# ARD.net
KiCad netlist of a schematic drawn in Altium Designer
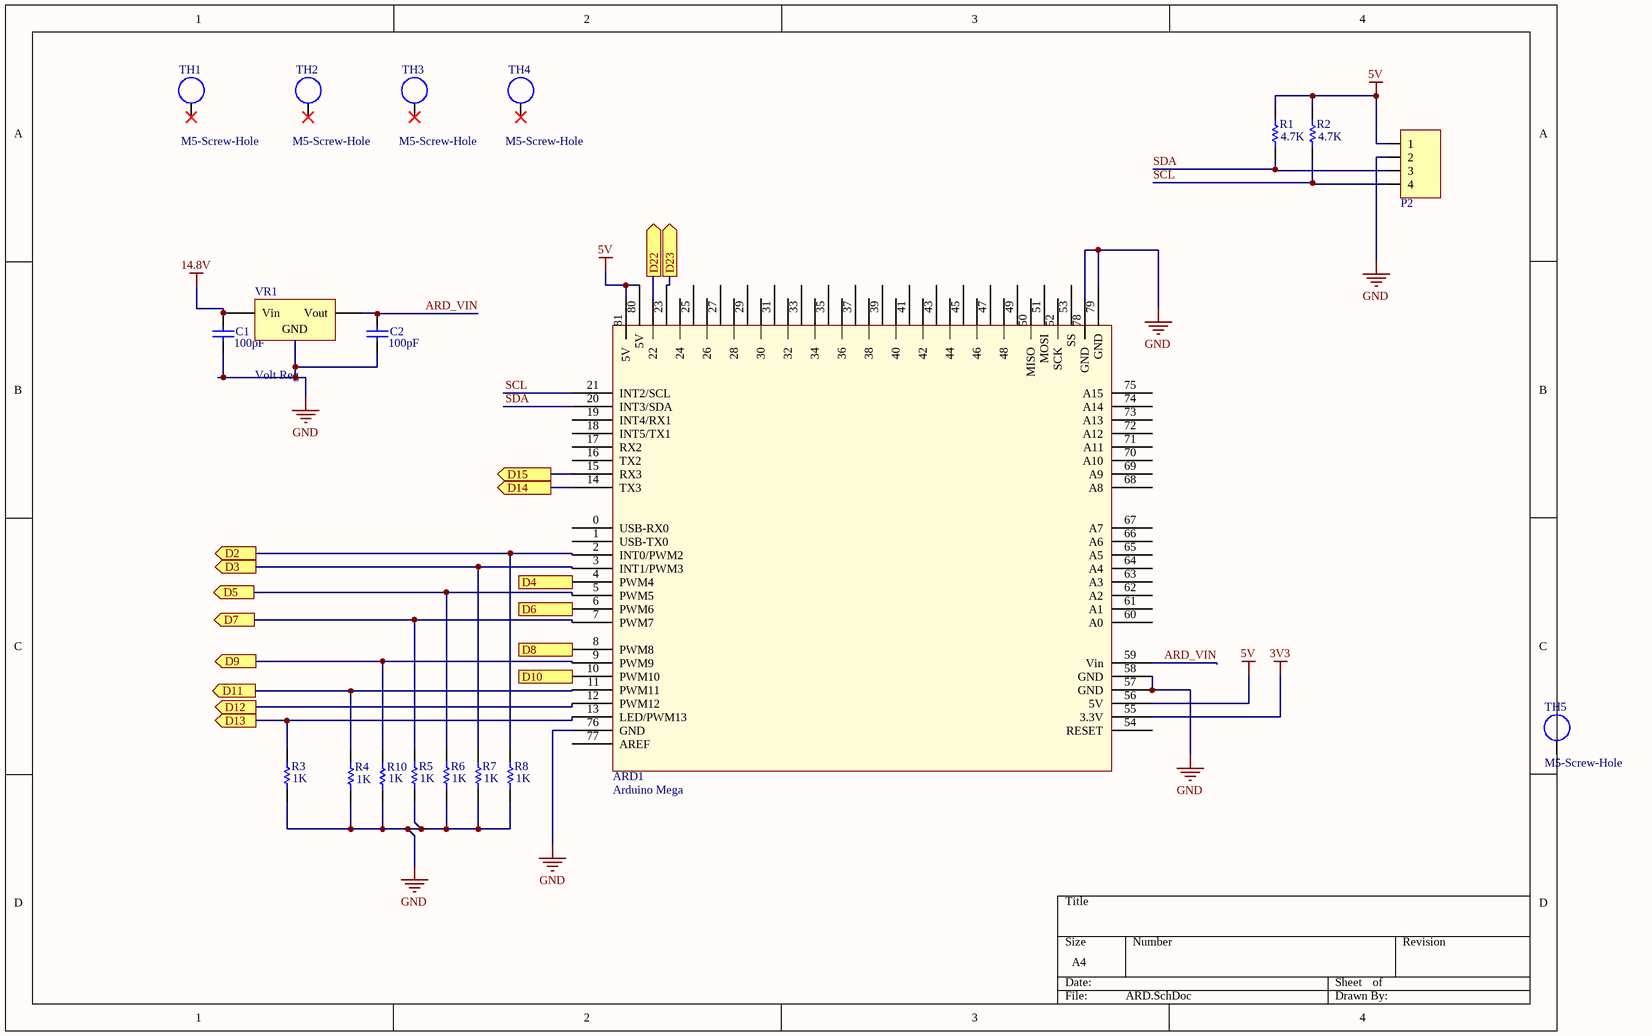
[diagram p0: ARD.SchDoc]

(export (version "E")
  (design (tool "Eeschema 10.0.6"))
  (components
    (comp (ref "ARD1")
      (value "Arduino Mega")
      (footprint "Arduino Mega")
      (libsource (lib "RSX_Modules") (part "Arduino Mega"))
    )
    (comp (ref "C1")
      (value "100pF")
      (footprint "C1206")
      (description "Capacitor (Semiconductor SIM Model)")
      (fields (field (name "Comment") "Cap Semi") (field (name "PUBLISHER") "Altium Limited"))
      (libsource (lib "Miscellaneous Devices") (part "Cap Semi"))
    )
    (comp (ref "C2")
      (value "100pF")
      (footprint "C1206")
      (description "Capacitor (Semiconductor SIM Model)")
      (fields (field (name "Comment") "Cap Semi") (field (name "PUBLISHER") "Altium Limited"))
      (libsource (lib "Miscellaneous Devices") (part "Cap Semi"))
    )
    (comp (ref "P2")
      (value "Mini-Fit Jr 4 Pos")
      (footprint "MOLEX 0039281043")
      (libsource (lib "RSX_Connectors") (part "Molex 0039281043"))
    )
    (comp (ref "R1")
      (value "4.7K")
      (footprint "RESC1608X06N_0603")
      (description "Resistor")
      (fields (field (name "Comment") "Res1") (field (name "PUBLISHER") "Altium Limited"))
      (libsource (lib "RSX_Resistors") (part "Res1"))
    )
    (comp (ref "R2")
      (value "4.7K")
      (footprint "RESC1608X06N_0603")
      (description "Resistor")
      (fields (field (name "Comment") "Res1") (field (name "PUBLISHER") "Altium Limited"))
      (libsource (lib "RSX_Resistors") (part "Res1"))
    )
    (comp (ref "R3")
      (value "1K")
      (footprint "RESC1608X06N_0603")
      (description "Resistor")
      (fields (field (name "Comment") "Res1") (field (name "PUBLISHER") "Altium Limited"))
      (libsource (lib "RSX_Resistors") (part "Res1"))
    )
    (comp (ref "R4")
      (value "1K")
      (footprint "RESC1608X06N_0603")
      (description "Resistor")
      (fields (field (name "Comment") "Res1") (field (name "PUBLISHER") "Altium Limited"))
      (libsource (lib "RSX_Resistors") (part "Res1"))
    )
    (comp (ref "R5")
      (value "1K")
      (footprint "RESC1608X06N_0603")
      (description "Resistor")
      (fields (field (name "Comment") "Res1") (field (name "PUBLISHER") "Altium Limited"))
      (libsource (lib "RSX_Resistors") (part "Res1"))
    )
    (comp (ref "R6")
      (value "1K")
      (footprint "RESC1608X06N_0603")
      (description "Resistor")
      (fields (field (name "Comment") "Res1") (field (name "PUBLISHER") "Altium Limited"))
      (libsource (lib "RSX_Resistors") (part "Res1"))
    )
    (comp (ref "R7")
      (value "1K")
      (footprint "RESC1608X06N_0603")
      (description "Resistor")
      (fields (field (name "Comment") "Res1") (field (name "PUBLISHER") "Altium Limited"))
      (libsource (lib "RSX_Resistors") (part "Res1"))
    )
    (comp (ref "R8")
      (value "1K")
      (footprint "RESC1608X06N_0603")
      (description "Resistor")
      (fields (field (name "Comment") "Res1") (field (name "PUBLISHER") "Altium Limited"))
      (libsource (lib "RSX_Resistors") (part "Res1"))
    )
    (comp (ref "R10")
      (value "1K")
      (footprint "RESC1608X06N_0603")
      (description "Resistor")
      (fields (field (name "Comment") "Res1") (field (name "PUBLISHER") "Altium Limited"))
      (libsource (lib "RSX_Resistors") (part "Res1"))
    )
    (comp (ref "TH1")
      (value "M5-Screw-Hole")
      (footprint "M5_Screw_Hole")
      (libsource (lib "RSX_Mechanicals") (part "M5-Screw-Hole"))
    )
    (comp (ref "TH2")
      (value "M5-Screw-Hole")
      (footprint "M5_Screw_Hole")
      (libsource (lib "RSX_Mechanicals") (part "M5-Screw-Hole"))
    )
    (comp (ref "TH3")
      (value "M5-Screw-Hole")
      (footprint "M5_Screw_Hole")
      (libsource (lib "RSX_Mechanicals") (part "M5-Screw-Hole"))
    )
    (comp (ref "TH4")
      (value "M5-Screw-Hole")
      (footprint "M5_Screw_Hole")
      (libsource (lib "RSX_Mechanicals") (part "M5-Screw-Hole"))
    )
    (comp (ref "TH5")
      (value "M5-Screw-Hole")
      (footprint "M5_Screw_Hole")
      (libsource (lib "RSX_Mechanicals") (part "M5-Screw-Hole"))
    )
    (comp (ref "VR1")
      (value "Volt Reg")
      (footprint "DPAK254P1420X457-3N")
      (description "Voltage Regulator")
      (fields (field (name "PUBLISHER") "Altium Limited"))
      (libsource (lib "RSX_ICs") (part "Volt Reg"))
    )
  )
  (nets
    (net (code "1") (name "/ARD_VIN") (class "Default")
      (node (ref "ARD1") (pin "59") (pinfunction "Vin_59") (pintype "passive"))
      (node (ref "C2") (pin "2") (pinfunction "2_2") (pintype "passive"))
      (node (ref "VR1") (pin "3") (pinfunction "Vout_3") (pintype "passive"))
    )
    (net (code "2") (name "/D2") (class "Default")
      (node (ref "ARD1") (pin "2") (pinfunction "INT0/PWM2_2") (pintype "passive"))
      (node (ref "R8") (pin "2") (pinfunction "2_2") (pintype "passive"))
    )
    (net (code "3") (name "/D3") (class "Default")
      (node (ref "ARD1") (pin "3") (pinfunction "INT1/PWM3_3") (pintype "passive"))
      (node (ref "R7") (pin "2") (pinfunction "2_2") (pintype "passive"))
    )
    (net (code "4") (name "/D4") (class "Default")
      (node (ref "ARD1") (pin "4") (pinfunction "PWM4_4") (pintype "passive"))
    )
    (net (code "5") (name "/D5") (class "Default")
      (node (ref "ARD1") (pin "5") (pinfunction "PWM5_5") (pintype "passive"))
      (node (ref "R6") (pin "2") (pinfunction "2_2") (pintype "passive"))
    )
    (net (code "6") (name "/D6") (class "Default")
      (node (ref "ARD1") (pin "6") (pinfunction "PWM6_6") (pintype "passive"))
    )
    (net (code "7") (name "/D7") (class "Default")
      (node (ref "ARD1") (pin "7") (pinfunction "PWM7_7") (pintype "passive"))
      (node (ref "R5") (pin "2") (pinfunction "2_2") (pintype "passive"))
    )
    (net (code "8") (name "/D8") (class "Default")
      (node (ref "ARD1") (pin "8") (pinfunction "PWM8_8") (pintype "passive"))
    )
    (net (code "9") (name "/D9") (class "Default")
      (node (ref "ARD1") (pin "9") (pinfunction "PWM9_9") (pintype "passive"))
      (node (ref "R10") (pin "2") (pinfunction "2_2") (pintype "passive"))
    )
    (net (code "10") (name "/D10") (class "Default")
      (node (ref "ARD1") (pin "10") (pinfunction "PWM10_10") (pintype "passive"))
    )
    (net (code "11") (name "/D11") (class "Default")
      (node (ref "ARD1") (pin "11") (pinfunction "PWM11_11") (pintype "passive"))
      (node (ref "R4") (pin "2") (pinfunction "2_2") (pintype "passive"))
    )
    (net (code "12") (name "/D12") (class "Default")
      (node (ref "ARD1") (pin "12") (pinfunction "PWM12_12") (pintype "passive"))
    )
    (net (code "13") (name "/D13") (class "Default")
      (node (ref "ARD1") (pin "13") (pinfunction "LED/PWM13_13") (pintype "passive"))
      (node (ref "R3") (pin "2") (pinfunction "2_2") (pintype "passive"))
    )
    (net (code "14") (name "/D14") (class "Default")
      (node (ref "ARD1") (pin "14") (pinfunction "TX3_14") (pintype "passive"))
    )
    (net (code "15") (name "/D15") (class "Default")
      (node (ref "ARD1") (pin "15") (pinfunction "RX3_15") (pintype "passive"))
    )
    (net (code "16") (name "/D22") (class "Default")
      (node (ref "ARD1") (pin "22") (pinfunction "22_22") (pintype "passive"))
    )
    (net (code "17") (name "/D23") (class "Default")
      (node (ref "ARD1") (pin "23") (pinfunction "23_23") (pintype "passive"))
    )
    (net (code "18") (name "/SCL") (class "Default")
      (node (ref "ARD1") (pin "21") (pinfunction "INT2/SCL_21") (pintype "passive"))
      (node (ref "P2") (pin "4") (pinfunction "4_4") (pintype "passive"))
      (node (ref "R2") (pin "1") (pinfunction "1_1") (pintype "passive"))
    )
    (net (code "19") (name "/SDA") (class "Default")
      (node (ref "ARD1") (pin "20") (pinfunction "INT3/SDA_20") (pintype "passive"))
      (node (ref "P2") (pin "3") (pinfunction "3_3") (pintype "passive"))
      (node (ref "R1") (pin "1") (pinfunction "1_1") (pintype "passive"))
    )
    (net (code "20") (name "3V3") (class "Default")
      (node (ref "ARD1") (pin "55") (pinfunction "3.3V_55") (pintype "passive"))
    )
    (net (code "21") (name "5V") (class "Default")
      (node (ref "ARD1") (pin "56") (pinfunction "5V_56") (pintype "passive"))
      (node (ref "ARD1") (pin "80") (pinfunction "5V_80") (pintype "passive"))
      (node (ref "ARD1") (pin "81") (pinfunction "5V_81") (pintype "passive"))
      (node (ref "P2") (pin "1") (pinfunction "1_1") (pintype "passive"))
      (node (ref "R1") (pin "2") (pinfunction "2_2") (pintype "passive"))
      (node (ref "R2") (pin "2") (pinfunction "2_2") (pintype "passive"))
    )
    (net (code "22") (name "14.8V") (class "Default")
      (node (ref "C1") (pin "2") (pinfunction "2_2") (pintype "passive"))
      (node (ref "VR1") (pin "1") (pinfunction "Vin_1") (pintype "passive"))
    )
    (net (code "23") (name "GND") (class "Default")
      (node (ref "ARD1") (pin "57") (pinfunction "GND_57") (pintype "passive"))
      (node (ref "ARD1") (pin "58") (pinfunction "GND_58") (pintype "passive"))
      (node (ref "ARD1") (pin "76") (pinfunction "GND_76") (pintype "passive"))
      (node (ref "ARD1") (pin "78") (pinfunction "GND_78") (pintype "passive"))
      (node (ref "ARD1") (pin "79") (pinfunction "GND_79") (pintype "passive"))
      (node (ref "C1") (pin "1") (pinfunction "1_1") (pintype "passive"))
      (node (ref "C2") (pin "1") (pinfunction "1_1") (pintype "passive"))
      (node (ref "P2") (pin "2") (pinfunction "2_2") (pintype "passive"))
      (node (ref "R10") (pin "1") (pinfunction "1_1") (pintype "passive"))
      (node (ref "R3") (pin "1") (pinfunction "1_1") (pintype "passive"))
      (node (ref "R4") (pin "1") (pinfunction "1_1") (pintype "passive"))
      (node (ref "R5") (pin "1") (pinfunction "1_1") (pintype "passive"))
      (node (ref "R6") (pin "1") (pinfunction "1_1") (pintype "passive"))
      (node (ref "R7") (pin "1") (pinfunction "1_1") (pintype "passive"))
      (node (ref "R8") (pin "1") (pinfunction "1_1") (pintype "passive"))
      (node (ref "VR1") (pin "2") (pinfunction "GND_2") (pintype "passive"))
    )
    (net (code "24") (name "unconnected-(ARD1-A0-Pad60)") (class "Default")
      (node (ref "ARD1") (pin "60") (pinfunction "A0_60") (pintype "passive"))
    )
    (net (code "25") (name "unconnected-(ARD1-A1-Pad61)") (class "Default")
      (node (ref "ARD1") (pin "61") (pinfunction "A1_61") (pintype "passive"))
    )
    (net (code "26") (name "unconnected-(ARD1-A2-Pad62)") (class "Default")
      (node (ref "ARD1") (pin "62") (pinfunction "A2_62") (pintype "passive"))
    )
    (net (code "27") (name "unconnected-(ARD1-A3-Pad63)") (class "Default")
      (node (ref "ARD1") (pin "63") (pinfunction "A3_63") (pintype "passive"))
    )
    (net (code "28") (name "unconnected-(ARD1-A4-Pad64)") (class "Default")
      (node (ref "ARD1") (pin "64") (pinfunction "A4_64") (pintype "passive"))
    )
    (net (code "29") (name "unconnected-(ARD1-A5-Pad65)") (class "Default")
      (node (ref "ARD1") (pin "65") (pinfunction "A5_65") (pintype "passive"))
    )
    (net (code "30") (name "unconnected-(ARD1-A6-Pad66)") (class "Default")
      (node (ref "ARD1") (pin "66") (pinfunction "A6_66") (pintype "passive"))
    )
    (net (code "31") (name "unconnected-(ARD1-A7-Pad67)") (class "Default")
      (node (ref "ARD1") (pin "67") (pinfunction "A7_67") (pintype "passive"))
    )
    (net (code "32") (name "unconnected-(ARD1-A8-Pad68)") (class "Default")
      (node (ref "ARD1") (pin "68") (pinfunction "A8_68") (pintype "passive"))
    )
    (net (code "33") (name "unconnected-(ARD1-A9-Pad69)") (class "Default")
      (node (ref "ARD1") (pin "69") (pinfunction "A9_69") (pintype "passive"))
    )
    (net (code "34") (name "unconnected-(ARD1-A10-Pad70)") (class "Default")
      (node (ref "ARD1") (pin "70") (pinfunction "A10_70") (pintype "passive"))
    )
    (net (code "35") (name "unconnected-(ARD1-A11-Pad71)") (class "Default")
      (node (ref "ARD1") (pin "71") (pinfunction "A11_71") (pintype "passive"))
    )
    (net (code "36") (name "unconnected-(ARD1-A12-Pad72)") (class "Default")
      (node (ref "ARD1") (pin "72") (pinfunction "A12_72") (pintype "passive"))
    )
    (net (code "37") (name "unconnected-(ARD1-A13-Pad73)") (class "Default")
      (node (ref "ARD1") (pin "73") (pinfunction "A13_73") (pintype "passive"))
    )
    (net (code "38") (name "unconnected-(ARD1-A14-Pad74)") (class "Default")
      (node (ref "ARD1") (pin "74") (pinfunction "A14_74") (pintype "passive"))
    )
    (net (code "39") (name "unconnected-(ARD1-A15-Pad75)") (class "Default")
      (node (ref "ARD1") (pin "75") (pinfunction "A15_75") (pintype "passive"))
    )
    (net (code "40") (name "unconnected-(ARD1-AREF-Pad77)") (class "Default")
      (node (ref "ARD1") (pin "77") (pinfunction "AREF_77") (pintype "passive"))
    )
    (net (code "41") (name "unconnected-(ARD1-INT4{slash}RX1-Pad19)") (class "Default")
      (node (ref "ARD1") (pin "19") (pinfunction "INT4/RX1_19") (pintype "passive"))
    )
    (net (code "42") (name "unconnected-(ARD1-INT5{slash}TX1-Pad18)") (class "Default")
      (node (ref "ARD1") (pin "18") (pinfunction "INT5/TX1_18") (pintype "passive"))
    )
    (net (code "43") (name "unconnected-(ARD1-MISO-Pad50)") (class "Default")
      (node (ref "ARD1") (pin "50") (pinfunction "MISO_50") (pintype "passive"))
    )
    (net (code "44") (name "unconnected-(ARD1-MOSI-Pad51)") (class "Default")
      (node (ref "ARD1") (pin "51") (pinfunction "MOSI_51") (pintype "passive"))
    )
    (net (code "45") (name "unconnected-(ARD1-Pad24)") (class "Default")
      (node (ref "ARD1") (pin "24") (pinfunction "24_24") (pintype "passive"))
    )
    (net (code "46") (name "unconnected-(ARD1-Pad25)") (class "Default")
      (node (ref "ARD1") (pin "25") (pinfunction "25_25") (pintype "passive"))
    )
    (net (code "47") (name "unconnected-(ARD1-Pad26)") (class "Default")
      (node (ref "ARD1") (pin "26") (pinfunction "26_26") (pintype "passive"))
    )
    (net (code "48") (name "unconnected-(ARD1-Pad27)") (class "Default")
      (node (ref "ARD1") (pin "27") (pinfunction "27_27") (pintype "passive"))
    )
    (net (code "49") (name "unconnected-(ARD1-Pad28)") (class "Default")
      (node (ref "ARD1") (pin "28") (pinfunction "28_28") (pintype "passive"))
    )
    (net (code "50") (name "unconnected-(ARD1-Pad29)") (class "Default")
      (node (ref "ARD1") (pin "29") (pinfunction "29_29") (pintype "passive"))
    )
    (net (code "51") (name "unconnected-(ARD1-Pad30)") (class "Default")
      (node (ref "ARD1") (pin "30") (pinfunction "30_30") (pintype "passive"))
    )
    (net (code "52") (name "unconnected-(ARD1-Pad31)") (class "Default")
      (node (ref "ARD1") (pin "31") (pinfunction "31_31") (pintype "passive"))
    )
    (net (code "53") (name "unconnected-(ARD1-Pad32)") (class "Default")
      (node (ref "ARD1") (pin "32") (pinfunction "32_32") (pintype "passive"))
    )
    (net (code "54") (name "unconnected-(ARD1-Pad33)") (class "Default")
      (node (ref "ARD1") (pin "33") (pinfunction "33_33") (pintype "passive"))
    )
    (net (code "55") (name "unconnected-(ARD1-Pad34)") (class "Default")
      (node (ref "ARD1") (pin "34") (pinfunction "34_34") (pintype "passive"))
    )
    (net (code "56") (name "unconnected-(ARD1-Pad35)") (class "Default")
      (node (ref "ARD1") (pin "35") (pinfunction "35_35") (pintype "passive"))
    )
    (net (code "57") (name "unconnected-(ARD1-Pad36)") (class "Default")
      (node (ref "ARD1") (pin "36") (pinfunction "36_36") (pintype "passive"))
    )
    (net (code "58") (name "unconnected-(ARD1-Pad37)") (class "Default")
      (node (ref "ARD1") (pin "37") (pinfunction "37_37") (pintype "passive"))
    )
    (net (code "59") (name "unconnected-(ARD1-Pad38)") (class "Default")
      (node (ref "ARD1") (pin "38") (pinfunction "38_38") (pintype "passive"))
    )
    (net (code "60") (name "unconnected-(ARD1-Pad39)") (class "Default")
      (node (ref "ARD1") (pin "39") (pinfunction "39_39") (pintype "passive"))
    )
    (net (code "61") (name "unconnected-(ARD1-Pad40)") (class "Default")
      (node (ref "ARD1") (pin "40") (pinfunction "40_40") (pintype "passive"))
    )
    (net (code "62") (name "unconnected-(ARD1-Pad41)") (class "Default")
      (node (ref "ARD1") (pin "41") (pinfunction "41_41") (pintype "passive"))
    )
    (net (code "63") (name "unconnected-(ARD1-Pad42)") (class "Default")
      (node (ref "ARD1") (pin "42") (pinfunction "42_42") (pintype "passive"))
    )
    (net (code "64") (name "unconnected-(ARD1-Pad43)") (class "Default")
      (node (ref "ARD1") (pin "43") (pinfunction "43_43") (pintype "passive"))
    )
    (net (code "65") (name "unconnected-(ARD1-Pad44)") (class "Default")
      (node (ref "ARD1") (pin "44") (pinfunction "44_44") (pintype "passive"))
    )
    (net (code "66") (name "unconnected-(ARD1-Pad45)") (class "Default")
      (node (ref "ARD1") (pin "45") (pinfunction "45_45") (pintype "passive"))
    )
    (net (code "67") (name "unconnected-(ARD1-Pad46)") (class "Default")
      (node (ref "ARD1") (pin "46") (pinfunction "46_46") (pintype "passive"))
    )
    (net (code "68") (name "unconnected-(ARD1-Pad47)") (class "Default")
      (node (ref "ARD1") (pin "47") (pinfunction "47_47") (pintype "passive"))
    )
    (net (code "69") (name "unconnected-(ARD1-Pad48)") (class "Default")
      (node (ref "ARD1") (pin "48") (pinfunction "48_48") (pintype "passive"))
    )
    (net (code "70") (name "unconnected-(ARD1-Pad49)") (class "Default")
      (node (ref "ARD1") (pin "49") (pinfunction "49_49") (pintype "passive"))
    )
    (net (code "71") (name "unconnected-(ARD1-RESET-Pad54)") (class "Default")
      (node (ref "ARD1") (pin "54") (pinfunction "RESET_54") (pintype "passive"))
    )
    (net (code "72") (name "unconnected-(ARD1-RX2-Pad17)") (class "Default")
      (node (ref "ARD1") (pin "17") (pinfunction "RX2_17") (pintype "passive"))
    )
    (net (code "73") (name "unconnected-(ARD1-SCK-Pad52)") (class "Default")
      (node (ref "ARD1") (pin "52") (pinfunction "SCK_52") (pintype "passive"))
    )
    (net (code "74") (name "unconnected-(ARD1-SS-Pad53)") (class "Default")
      (node (ref "ARD1") (pin "53") (pinfunction "SS_53") (pintype "passive"))
    )
    (net (code "75") (name "unconnected-(ARD1-TX2-Pad16)") (class "Default")
      (node (ref "ARD1") (pin "16") (pinfunction "TX2_16") (pintype "passive"))
    )
    (net (code "76") (name "unconnected-(ARD1-USB-RX0-Pad0)") (class "Default")
      (node (ref "ARD1") (pin "0") (pinfunction "USB-RX0_0") (pintype "passive"))
    )
    (net (code "77") (name "unconnected-(ARD1-USB-TX0-Pad1)") (class "Default")
      (node (ref "ARD1") (pin "1") (pinfunction "USB-TX0_1") (pintype "passive"))
    )
    (net (code "78") (name "unconnected-(TH1-Pad1)") (class "Default")
      (node (ref "TH1") (pin "1") (pinfunction "1_1") (pintype "passive+no_connect"))
    )
    (net (code "79") (name "unconnected-(TH2-Pad1)") (class "Default")
      (node (ref "TH2") (pin "1") (pinfunction "1_1") (pintype "passive+no_connect"))
    )
    (net (code "80") (name "unconnected-(TH3-Pad1)") (class "Default")
      (node (ref "TH3") (pin "1") (pinfunction "1_1") (pintype "passive+no_connect"))
    )
    (net (code "81") (name "unconnected-(TH4-Pad1)") (class "Default")
      (node (ref "TH4") (pin "1") (pinfunction "1_1") (pintype "passive+no_connect"))
    )
    (net (code "82") (name "unconnected-(TH5-Pad1)") (class "Default")
      (node (ref "TH5") (pin "1") (pinfunction "1_1") (pintype "passive"))
    )
  )
)
